# Sheet3.net
KiCad netlist of a schematic drawn in Altium Designer
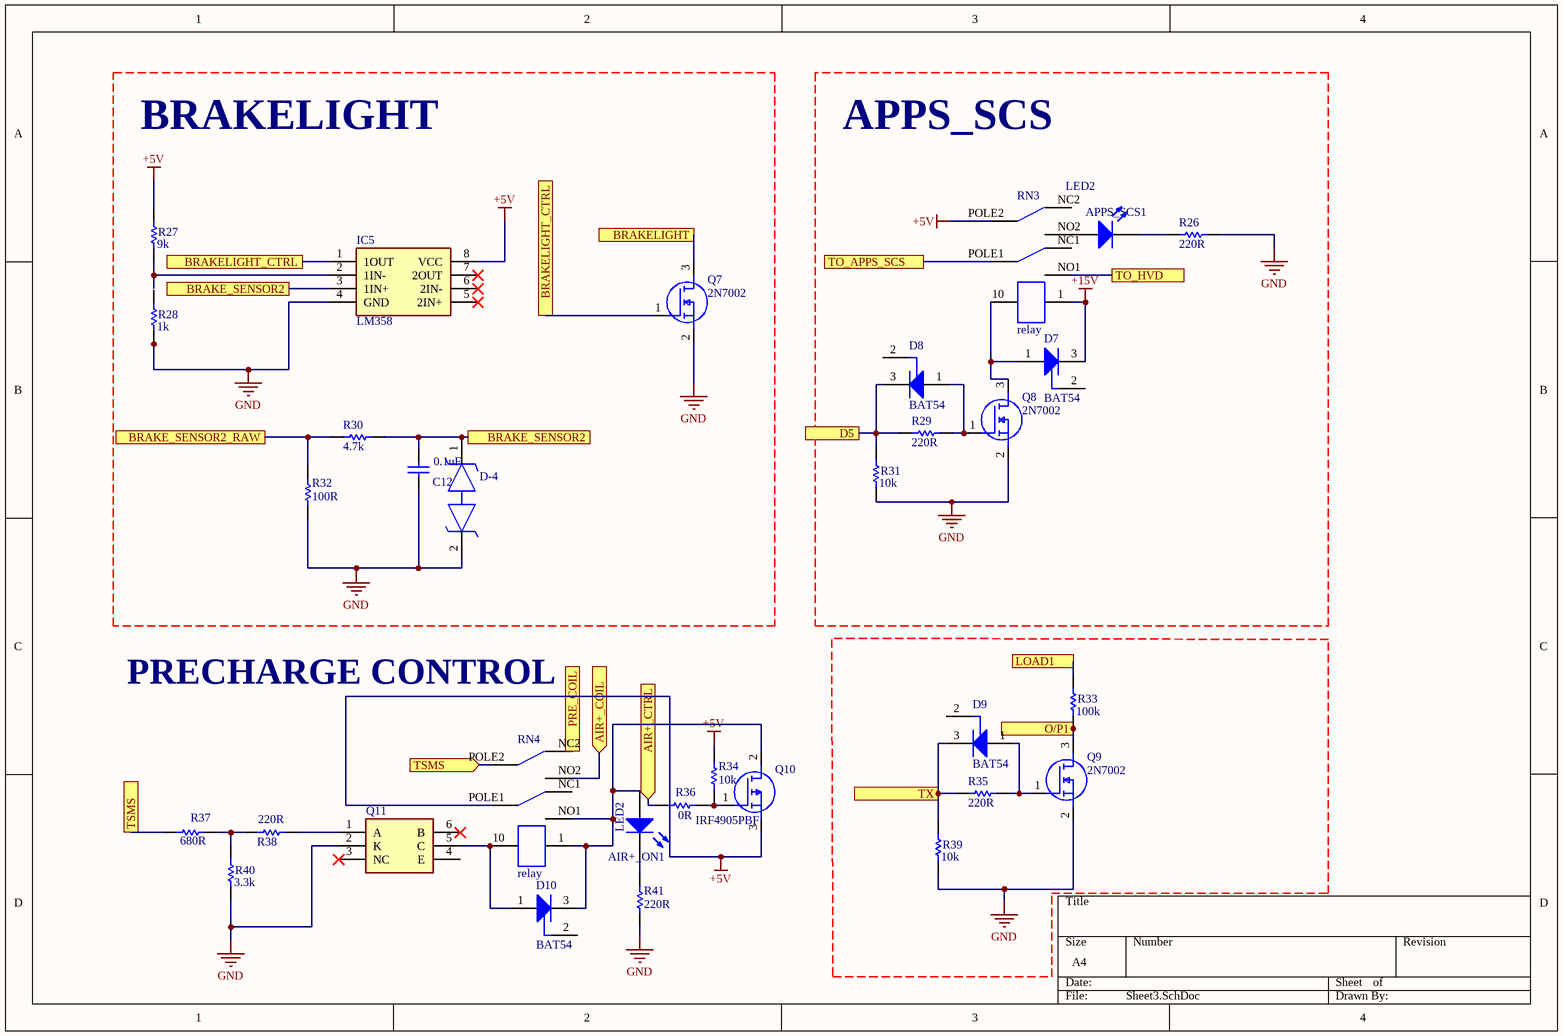
[diagram p0: Sheet3.SchDoc]

(export (version "E")
  (design (tool "Eeschema 10.0.6"))
  (components
    (comp (ref "AIR+_ON1")
      (value "LED2")
      (footprint "3.2X1.6X1.1")
      (description "Typical RED, GREEN, YELLOW, AMBER GaAs LED")
      (fields (field (name "PUBLISHER") "Altium Limited"))
      (libsource (lib "Miscellaneous Devices") (part "LED2"))
    )
    (comp (ref "APPS_SCS1")
      (value "LED2")
      (footprint "3.2X1.6X1.1")
      (description "Typical RED, GREEN, YELLOW, AMBER GaAs LED")
      (fields (field (name "PUBLISHER") "Altium Limited"))
      (libsource (lib "Miscellaneous Devices") (part "LED2"))
    )
    (comp (ref "C12")
      (value "0.1uF")
      (footprint "KEMT-1206-2_N")
      (description "CAP, Ceramic, 0.1 uF, +/- 10%, 50 V, -55 to 125 degC, 1206 (3216 Metric), RoHS, Tape and Reel")
      (fields (field (name "MANUFACTURER") "Kemet"))
      (libsource (lib "TSAL LV Schlib") (part "CAPACITOR"))
    )
    (comp (ref "D-4")
      (value "TPD1E6B06DPLR")
      (footprint "R1206")
      (libsource (lib "Diode_Texas_Instruments_TPD1E6B06DPLR_eec") (part "TPD1E6B06DPLR"))
    )
    (comp (ref "D7")
      (value "BAT54")
      (footprint "INF-SOT23_N")
      (description "Silicon Schottky Diode, SOT23, Reel, Green")
      (fields (field (name "MANUFACTURER") "Infineon"))
      (libsource (lib "Schlib1") (part "CMP-1182-00010-1"))
    )
    (comp (ref "D8")
      (value "BAT54")
      (footprint "INF-SOT23_N")
      (description "Silicon Schottky Diode, SOT23, Reel, Green")
      (fields (field (name "MANUFACTURER") "Infineon"))
      (libsource (lib "Schlib1") (part "CMP-1182-00010-1"))
    )
    (comp (ref "D9")
      (value "BAT54")
      (footprint "INF-SOT23_N")
      (description "Silicon Schottky Diode, SOT23, Reel, Green")
      (fields (field (name "MANUFACTURER") "Infineon"))
      (libsource (lib "Schlib1") (part "CMP-1182-00010-1"))
    )
    (comp (ref "D10")
      (value "BAT54")
      (footprint "INF-SOT23_N")
      (description "Silicon Schottky Diode, SOT23, Reel, Green")
      (fields (field (name "MANUFACTURER") "Infineon"))
      (libsource (lib "Schlib1") (part "CMP-1182-00010-1"))
    )
    (comp (ref "IC5")
      (value "LM358")
      (footprint "SamacSys:SOP100P600X150-8N")
      (description "Integrated Circuit")
      (libsource (lib "SamacSys") (part "LM358"))
    )
    (comp (ref "Q7")
      (value "2N7002")
      (footprint "SamacSys:SOT96P240X120-3N")
      (description "MOSFET (N-Channel)")
      (fields (field (name "MOUSER PART NUMBER") "781-2N7002"))
      (libsource (lib "SamacSys") (part "2N7002"))
    )
    (comp (ref "Q8")
      (value "2N7002")
      (footprint "SamacSys:SOT96P240X120-3N")
      (description "MOSFET (N-Channel)")
      (fields (field (name "MOUSER PART NUMBER") "781-2N7002"))
      (libsource (lib "SamacSys") (part "2N7002"))
    )
    (comp (ref "Q9")
      (value "2N7002")
      (footprint "SamacSys:SOT96P240X120-3N")
      (description "MOSFET (N-Channel)")
      (fields (field (name "MOUSER PART NUMBER") "781-2N7002"))
      (libsource (lib "*") (part "2N7002"))
    )
    (comp (ref "Q10")
      (value "IRF4905PBF")
      (footprint "SamacSys:TO254P469X1042X1967-3P")
      (description "MOSFET (P-Channel)")
      (fields (field (name "MOUSER PART NUMBER") "942-IRF4905PBF"))
      (libsource (lib "SamacSys") (part "IRF4905PBF"))
    )
    (comp (ref "Q11")
      (value "MCT2ESM")
      (footprint "SamacSys:SOT254P916X480-6N")
      (description "Phototransistor")
      (fields (field (name "MOUSER PART NUMBER") "512-MCT2ESM"))
      (libsource (lib "SamacSys") (part "MCT2ESM"))
    )
    (comp (ref "R26")
      (value "220R")
      (footprint "RESC3216X60X45NL10T20 - duplicate")
      (fields (field (name "PART NUMBER") "CRCW120647K0FKEA") (field (name "MANUFACTURER") "Vishay Dale"))
      (libsource (lib "Schlib1") (part "CMP-2003-02213-1"))
    )
    (comp (ref "R27")
      (value "9k")
      (footprint "RESC3216X60X45NL10T20 - duplicate")
      (fields (field (name "PART NUMBER") "CRCW120647K0FKEA") (field (name "MANUFACTURER") "Vishay Dale"))
      (libsource (lib "Schlib1") (part "CMP-2003-02213-1"))
    )
    (comp (ref "R28")
      (value "1k")
      (footprint "RESC3216X60X45NL10T20 - duplicate")
      (fields (field (name "PART NUMBER") "CRCW120647K0FKEA") (field (name "MANUFACTURER") "Vishay Dale"))
      (libsource (lib "Schlib1") (part "CMP-2003-02213-1"))
    )
    (comp (ref "R29")
      (value "220R")
      (footprint "RESC3216X60X45NL10T20 - duplicate")
      (fields (field (name "PART NUMBER") "CRCW120647K0FKEA") (field (name "MANUFACTURER") "Vishay Dale"))
      (libsource (lib "Schlib1") (part "CMP-2003-02213-1"))
    )
    (comp (ref "R30")
      (value "4.7k")
      (footprint "RESC3216X60X45NL10T20 - duplicate")
      (fields (field (name "PART NUMBER") "CRCW120647K0FKEA") (field (name "MANUFACTURER") "Vishay Dale"))
      (libsource (lib "Schlib1") (part "CMP-2003-02213-1"))
    )
    (comp (ref "R31")
      (value "10k")
      (footprint "RESC3216X60X45NL10T20 - duplicate")
      (fields (field (name "PART NUMBER") "CRCW120647K0FKEA") (field (name "MANUFACTURER") "Vishay Dale"))
      (libsource (lib "Schlib1") (part "CMP-2003-02213-1"))
    )
    (comp (ref "R32")
      (value "100R")
      (footprint "RESC3216X60X45NL10T20 - duplicate")
      (fields (field (name "PART NUMBER") "CRCW120647K0FKEA") (field (name "MANUFACTURER") "Vishay Dale"))
      (libsource (lib "Schlib1") (part "CMP-2003-02213-1"))
    )
    (comp (ref "R33")
      (value "100k")
      (footprint "RESC3216X60X45NL10T20 - duplicate")
      (fields (field (name "PART NUMBER") "CRCW120647K0FKEA") (field (name "MANUFACTURER") "Vishay Dale"))
      (libsource (lib "Schlib1") (part "CMP-2003-02213-1"))
    )
    (comp (ref "R34")
      (value "10k")
      (footprint "R1206")
      (fields (field (name "PART NUMBER") "CRCW120647K0FKEA") (field (name "MANUFACTURER") "Vishay Dale"))
      (libsource (lib "Schlib1") (part "RES"))
    )
    (comp (ref "R35")
      (value "220R")
      (footprint "RESC3216X60X45NL10T20 - duplicate")
      (fields (field (name "PART NUMBER") "CRCW120647K0FKEA") (field (name "MANUFACTURER") "Vishay Dale"))
      (libsource (lib "Schlib1") (part "CMP-2003-02213-1"))
    )
    (comp (ref "R36")
      (value "0R")
      (footprint "R1206")
      (fields (field (name "PART NUMBER") "CRCW120647K0FKEA") (field (name "MANUFACTURER") "Vishay Dale"))
      (libsource (lib "Schlib1") (part "RES"))
    )
    (comp (ref "R37")
      (value "680R")
      (footprint "RESC3216X60X45NL10T20 - duplicate")
      (fields (field (name "PART NUMBER") "CRCW120647K0FKEA") (field (name "MANUFACTURER") "Vishay Dale"))
      (libsource (lib "Schlib1") (part "CMP-2003-02213-1"))
    )
    (comp (ref "R38")
      (value "220R")
      (footprint "RESC3216X60X45NL10T20 - duplicate")
      (fields (field (name "PART NUMBER") "CRCW120647K0FKEA") (field (name "MANUFACTURER") "Vishay Dale"))
      (libsource (lib "Schlib1") (part "CMP-2003-02213-1"))
    )
    (comp (ref "R39")
      (value "10k")
      (footprint "RESC3216X60X45NL10T20 - duplicate")
      (fields (field (name "PART NUMBER") "CRCW120647K0FKEA") (field (name "MANUFACTURER") "Vishay Dale"))
      (libsource (lib "Schlib1") (part "CMP-2003-02213-1"))
    )
    (comp (ref "R40")
      (value "3.3k")
      (footprint "RESC3216X60X45NL10T20 - duplicate")
      (fields (field (name "PART NUMBER") "CRCW120647K0FKEA") (field (name "MANUFACTURER") "Vishay Dale"))
      (libsource (lib "Schlib1") (part "CMP-2003-02213-1"))
    )
    (comp (ref "R41")
      (value "220R")
      (footprint "R1206")
      (fields (field (name "PART NUMBER") "CRCW120647K0FKEA") (field (name "MANUFACTURER") "Vishay Dale"))
      (libsource (lib "Schlib1") (part "RES"))
    )
    (comp (ref "RN3") (value "relay") (footprint "relaytq") (libsource (lib "Schlib1") (part "relay")))
    (comp (ref "RN4") (value "relay") (footprint "relaytq") (libsource (lib "Schlib1") (part "relay")))
  )
  (nets
    (net (code "1") (name "+5V") (class "Default")
      (node (ref "IC5") (pin "8") (pinfunction "VCC_8") (pintype "passive"))
      (node (ref "Q10") (pin "3") (pinfunction "S_3") (pintype "passive"))
      (node (ref "R27") (pin "2") (pinfunction "2_2") (pintype "passive"))
      (node (ref "R34") (pin "2") (pinfunction "2_2") (pintype "passive"))
      (node (ref "RN3") (pin "POLE2") (pinfunction "POLE2_POLE2") (pintype "passive"))
      (node (ref "RN4") (pin "POLE1") (pinfunction "POLE1_POLE1") (pintype "passive"))
    )
    (net (code "2") (name "+15V") (class "Default")
      (node (ref "D7") (pin "3") (pinfunction "K_3") (pintype "passive"))
      (node (ref "RN3") (pin "1") (pinfunction "1_1") (pintype "passive"))
    )
    (net (code "3") (name "/AIR+_COIL") (class "Default")
      (node (ref "RN4") (pin "NO2") (pinfunction "NO2_NO2") (pintype "passive"))
    )
    (net (code "4") (name "/AIR+_CTRL") (class "Default")
      (node (ref "R36") (pin "1") (pinfunction "1_1") (pintype "passive"))
    )
    (net (code "5") (name "/BRAKELIGHT") (class "Default")
      (node (ref "Q7") (pin "3") (pinfunction "D_3") (pintype "passive"))
    )
    (net (code "6") (name "/BRAKELIGHT_CTRL") (class "Default")
      (node (ref "IC5") (pin "1") (pinfunction "1OUT_1") (pintype "passive"))
      (node (ref "Q7") (pin "1") (pinfunction "G_1") (pintype "passive"))
    )
    (net (code "7") (name "/BRAKE_SENSOR2") (class "Default")
      (node (ref "C12") (pin "2") (pinfunction "2_2") (pintype "passive"))
      (node (ref "D-4") (pin "1") (pinfunction "1_1") (pintype "passive"))
      (node (ref "IC5") (pin "3") (pinfunction "1IN+_3") (pintype "passive"))
      (node (ref "R30") (pin "1") (pinfunction "1_1") (pintype "passive"))
    )
    (net (code "8") (name "/BRAKE_SENSOR2_RAW") (class "Default")
      (node (ref "R30") (pin "2") (pinfunction "2_2") (pintype "passive"))
      (node (ref "R32") (pin "1") (pinfunction "1_1") (pintype "passive"))
    )
    (net (code "9") (name "/D5") (class "Default")
      (node (ref "D8") (pin "3") (pinfunction "K_3") (pintype "passive"))
      (node (ref "R29") (pin "2") (pinfunction "2_2") (pintype "passive"))
      (node (ref "R31") (pin "2") (pinfunction "2_2") (pintype "passive"))
    )
    (net (code "10") (name "/LOAD1") (class "Default")
      (node (ref "R33") (pin "2") (pinfunction "2_2") (pintype "passive"))
    )
    (net (code "11") (name "/O{slash}P1") (class "Default")
      (node (ref "Q9") (pin "3") (pinfunction "D_3") (pintype "passive"))
      (node (ref "R33") (pin "1") (pinfunction "1_1") (pintype "passive"))
    )
    (net (code "12") (name "/PRE_COIL") (class "Default")
      (node (ref "RN4") (pin "NC2") (pinfunction "NC2_NC2") (pintype "passive"))
    )
    (net (code "13") (name "/TO_APPS_SCS") (class "Default")
      (node (ref "RN3") (pin "POLE1") (pinfunction "POLE1_POLE1") (pintype "passive"))
    )
    (net (code "14") (name "/TO_HVD") (class "Default")
      (node (ref "RN3") (pin "NO1") (pinfunction "NO1_NO1") (pintype "passive"))
    )
    (net (code "15") (name "/TSMS") (class "Default")
      (node (ref "R37") (pin "2") (pinfunction "2_2") (pintype "passive"))
      (node (ref "RN4") (pin "POLE2") (pinfunction "POLE2_POLE2") (pintype "passive"))
    )
    (net (code "16") (name "/TX") (class "Default")
      (node (ref "D9") (pin "3") (pinfunction "K_3") (pintype "passive"))
      (node (ref "R35") (pin "2") (pinfunction "2_2") (pintype "passive"))
      (node (ref "R39") (pin "2") (pinfunction "2_2") (pintype "passive"))
    )
    (net (code "17") (name "GND") (class "Default")
      (node (ref "C12") (pin "1") (pinfunction "1_1") (pintype "passive"))
      (node (ref "D-4") (pin "2") (pinfunction "2_2") (pintype "passive"))
      (node (ref "IC5") (pin "4") (pinfunction "GND_4") (pintype "passive"))
      (node (ref "Q11") (pin "2") (pinfunction "K_2") (pintype "passive"))
      (node (ref "Q7") (pin "2") (pinfunction "S_2") (pintype "passive"))
      (node (ref "Q8") (pin "2") (pinfunction "S_2") (pintype "passive"))
      (node (ref "Q9") (pin "2") (pinfunction "S_2") (pintype "passive"))
      (node (ref "R26") (pin "1") (pinfunction "1_1") (pintype "passive"))
      (node (ref "R28") (pin "1") (pinfunction "1_1") (pintype "passive"))
      (node (ref "R31") (pin "1") (pinfunction "1_1") (pintype "passive"))
      (node (ref "R32") (pin "2") (pinfunction "2_2") (pintype "passive"))
      (node (ref "R39") (pin "1") (pinfunction "1_1") (pintype "passive"))
      (node (ref "R40") (pin "1") (pinfunction "1_1") (pintype "passive"))
      (node (ref "R41") (pin "2") (pinfunction "2_2") (pintype "passive"))
    )
    (net (code "18") (name "Net-(AIR+_ON1-A)") (class "Default")
      (node (ref "AIR+_ON1") (pin "1") (pinfunction "A_1") (pintype "passive"))
      (node (ref "D10") (pin "3") (pinfunction "K_3") (pintype "passive"))
      (node (ref "Q10") (pin "2") (pinfunction "D_2") (pintype "passive"))
      (node (ref "RN4") (pin "1") (pinfunction "1_1") (pintype "passive"))
      (node (ref "RN4") (pin "NO1") (pinfunction "NO1_NO1") (pintype "passive"))
    )
    (net (code "19") (name "Net-(AIR+_ON1-K)") (class "Default")
      (node (ref "AIR+_ON1") (pin "2") (pinfunction "K_2") (pintype "passive"))
      (node (ref "R41") (pin "1") (pinfunction "1_1") (pintype "passive"))
    )
    (net (code "20") (name "Net-(APPS_SCS1-A)") (class "Default")
      (node (ref "APPS_SCS1") (pin "1") (pinfunction "A_1") (pintype "passive"))
      (node (ref "RN3") (pin "NO2") (pinfunction "NO2_NO2") (pintype "passive"))
    )
    (net (code "21") (name "Net-(APPS_SCS1-K)") (class "Default")
      (node (ref "APPS_SCS1") (pin "2") (pinfunction "K_2") (pintype "passive"))
      (node (ref "R26") (pin "2") (pinfunction "2_2") (pintype "passive"))
    )
    (net (code "22") (name "Net-(D7-A)") (class "Default")
      (node (ref "D7") (pin "1") (pinfunction "A_1") (pintype "passive"))
      (node (ref "Q8") (pin "3") (pinfunction "D_3") (pintype "passive"))
      (node (ref "RN3") (pin "10") (pinfunction "10_10") (pintype "passive"))
    )
    (net (code "23") (name "Net-(D8-A)") (class "Default")
      (node (ref "D8") (pin "1") (pinfunction "A_1") (pintype "passive"))
      (node (ref "Q8") (pin "1") (pinfunction "G_1") (pintype "passive"))
      (node (ref "R29") (pin "1") (pinfunction "1_1") (pintype "passive"))
    )
    (net (code "24") (name "Net-(D9-A)") (class "Default")
      (node (ref "D9") (pin "1") (pinfunction "A_1") (pintype "passive"))
      (node (ref "Q9") (pin "1") (pinfunction "G_1") (pintype "passive"))
      (node (ref "R35") (pin "1") (pinfunction "1_1") (pintype "passive"))
    )
    (net (code "25") (name "Net-(D10-A)") (class "Default")
      (node (ref "D10") (pin "1") (pinfunction "A_1") (pintype "passive"))
      (node (ref "Q11") (pin "5") (pinfunction "C_5") (pintype "passive"))
      (node (ref "RN4") (pin "10") (pinfunction "10_10") (pintype "passive"))
    )
    (net (code "26") (name "Net-(IC5-1IN-)") (class "Default")
      (node (ref "IC5") (pin "2") (pinfunction "1IN-_2") (pintype "passive"))
      (node (ref "R27") (pin "1") (pinfunction "1_1") (pintype "passive"))
    )
    (net (code "27") (name "Net-(Q10-G)") (class "Default")
      (node (ref "Q10") (pin "1") (pinfunction "G_1") (pintype "passive"))
      (node (ref "R34") (pin "1") (pinfunction "1_1") (pintype "passive"))
      (node (ref "R36") (pin "2") (pinfunction "2_2") (pintype "passive"))
    )
    (net (code "28") (name "Net-(Q11-A)") (class "Default")
      (node (ref "Q11") (pin "1") (pinfunction "A_1") (pintype "passive"))
      (node (ref "R38") (pin "1") (pinfunction "1_1") (pintype "passive"))
    )
    (net (code "29") (name "Net-(R37-Pad1)") (class "Default")
      (node (ref "R37") (pin "1") (pinfunction "1_1") (pintype "passive"))
      (node (ref "R38") (pin "2") (pinfunction "2_2") (pintype "passive"))
      (node (ref "R40") (pin "2") (pinfunction "2_2") (pintype "passive"))
    )
    (net (code "30") (name "unconnected-(D7-NC-Pad2)") (class "Default")
      (node (ref "D7") (pin "2") (pinfunction "NC_2") (pintype "passive"))
    )
    (net (code "31") (name "unconnected-(D8-NC-Pad2)") (class "Default")
      (node (ref "D8") (pin "2") (pinfunction "NC_2") (pintype "passive"))
    )
    (net (code "32") (name "unconnected-(D9-NC-Pad2)") (class "Default")
      (node (ref "D9") (pin "2") (pinfunction "NC_2") (pintype "passive"))
    )
    (net (code "33") (name "unconnected-(D10-NC-Pad2)") (class "Default")
      (node (ref "D10") (pin "2") (pinfunction "NC_2") (pintype "passive"))
    )
    (net (code "34") (name "unconnected-(IC5-2IN+-Pad5)") (class "Default")
      (node (ref "IC5") (pin "5") (pinfunction "2IN+_5") (pintype "passive+no_connect"))
    )
    (net (code "35") (name "unconnected-(IC5-2IN--Pad6)") (class "Default")
      (node (ref "IC5") (pin "6") (pinfunction "2IN-_6") (pintype "passive+no_connect"))
    )
    (net (code "36") (name "unconnected-(IC5-2OUT-Pad7)") (class "Default")
      (node (ref "IC5") (pin "7") (pinfunction "2OUT_7") (pintype "passive+no_connect"))
    )
    (net (code "37") (name "unconnected-(Q11-B-Pad6)") (class "Default")
      (node (ref "Q11") (pin "6") (pinfunction "B_6") (pintype "passive+no_connect"))
    )
    (net (code "38") (name "unconnected-(Q11-E-Pad4)") (class "Default")
      (node (ref "Q11") (pin "4") (pinfunction "E_4") (pintype "passive"))
    )
    (net (code "39") (name "unconnected-(Q11-NC-Pad3)") (class "Default")
      (node (ref "Q11") (pin "3") (pinfunction "NC_3") (pintype "passive+no_connect"))
    )
    (net (code "40") (name "unconnected-(R28-Pad2)") (class "Default")
      (node (ref "R28") (pin "2") (pinfunction "2_2") (pintype "passive"))
    )
    (net (code "41") (name "unconnected-(RN3-PadNC1)") (class "Default")
      (node (ref "RN3") (pin "NC1") (pinfunction "NC1_NC1") (pintype "passive"))
    )
    (net (code "42") (name "unconnected-(RN3-PadNC2)") (class "Default")
      (node (ref "RN3") (pin "NC2") (pinfunction "NC2_NC2") (pintype "passive"))
    )
    (net (code "43") (name "unconnected-(RN4-PadNC1)") (class "Default")
      (node (ref "RN4") (pin "NC1") (pinfunction "NC1_NC1") (pintype "passive"))
    )
  )
)
